# Motor_Header.net
KiCad netlist of a schematic drawn in Altium Designer
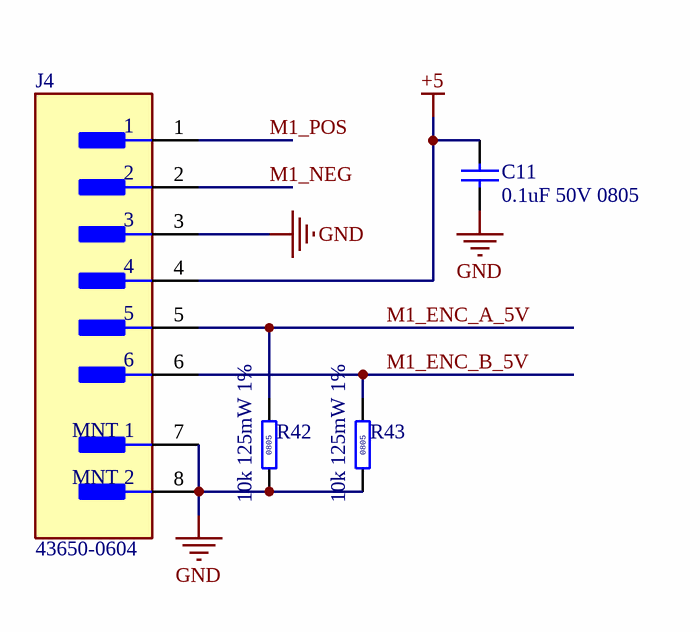
[diagram p0: Motor_Header.SchDoc]

(export (version "E")
  (design (tool "Eeschema 10.0.6"))
  (components
    (comp (ref "C11")
      (value "0.1uF 50V 0805")
      (footprint "CAPC2012X14N")
      (description "Cap, SMD, 0.1uF, 50V, 10%, 0805, X7R")
      (fields
        (field (name "MANUFACTURER") "Samsung")
        (field (name "MANUFACTURERPARTNUMBER") "CL21B104KBCWPNC")
      )
      (libsource (lib "Andor Technology") (part "CAP"))
    )
    (comp (ref "J4")
      (value "43650-0604")
      (footprint "FP-43650-0604-MFG")
      (description "43650-0604 Conn Power HDR 6 POS 3mm Solder RA Thru-Hole 6 Terminal 1 Port Micro-Fit 3.0™ Frame")
      (libsource (lib "Altium Content Vault") (part "ed24c53d9ba001d1a2a686240a95171"))
    )
    (comp (ref "R42")
      (value "10k 125mW 1%")
      (footprint "RESC2013X60X35ML10T20")
      (description "Res, SMD, 10k, 125mW, 1%, ±200ppm, 0805")
      (fields
        (field (name "MANUFACTURER") "Panasonic")
        (field (name "MANUFACTURERPARTNUMBER") "ERJ-6GEYJ103V")
      )
      (libsource (lib "Andor Technology") (part "Resistor_0805"))
    )
    (comp (ref "R43")
      (value "10k 125mW 1%")
      (footprint "RESC2013X60X35ML10T20")
      (description "Res, SMD, 10k, 125mW, 1%, ±200ppm, 0805")
      (fields
        (field (name "MANUFACTURER") "Panasonic")
        (field (name "MANUFACTURERPARTNUMBER") "ERJ-6GEYJ103V")
      )
      (libsource (lib "Andor Technology") (part "Resistor_0805"))
    )
  )
  (nets
    (net (code "1") (name "+5") (class "Default")
      (node (ref "C11") (pin "2") (pinfunction "2_2") (pintype "passive"))
      (node (ref "J4") (pin "4") (pinfunction "4_4") (pintype "passive"))
    )
    (net (code "2") (name "/M1_ENC_A_5V") (class "Default")
      (node (ref "J4") (pin "5") (pinfunction "5_5") (pintype "passive"))
      (node (ref "R42") (pin "2") (pinfunction "2_2") (pintype "passive"))
    )
    (net (code "3") (name "/M1_ENC_B_5V") (class "Default")
      (node (ref "J4") (pin "6") (pinfunction "6_6") (pintype "passive"))
      (node (ref "R43") (pin "2") (pinfunction "2_2") (pintype "passive"))
    )
    (net (code "4") (name "/M1_NEG") (class "Default")
      (node (ref "J4") (pin "2") (pinfunction "2_2") (pintype "passive"))
    )
    (net (code "5") (name "/M1_POS") (class "Default")
      (node (ref "J4") (pin "1") (pinfunction "1_1") (pintype "passive"))
    )
    (net (code "6") (name "GND") (class "Default")
      (node (ref "C11") (pin "1") (pinfunction "1_1") (pintype "passive"))
      (node (ref "J4") (pin "3") (pinfunction "3_3") (pintype "passive"))
      (node (ref "J4") (pin "7") (pinfunction "MNT_1_7") (pintype "passive"))
      (node (ref "J4") (pin "8") (pinfunction "MNT_2_8") (pintype "passive"))
      (node (ref "R42") (pin "1") (pinfunction "1_1") (pintype "passive"))
      (node (ref "R43") (pin "1") (pinfunction "1_1") (pintype "passive"))
    )
  )
)
